# Sheet1.net
KiCad netlist of a schematic drawn in Altium Designer
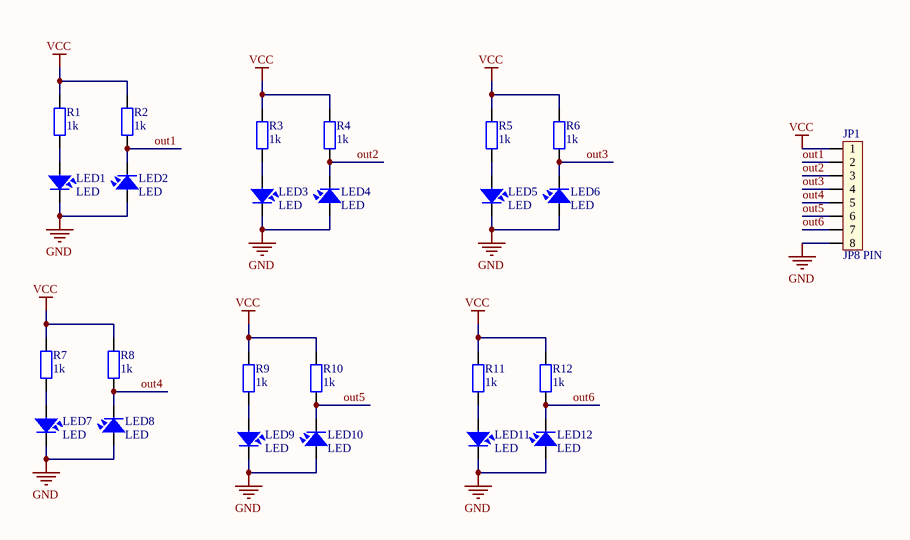
[diagram p0: Sheet1.SchDoc]

(export (version "E")
  (design (tool "Eeschema 10.0.6"))
  (components
    (comp (ref "JP1") (value "JP8 PIN") (footprint "JP8") (libsource (lib "syhaunguyen") (part "JP8")))
    (comp (ref "LED1")
      (value "LED")
      (footprint "LED-3")
      (description "LED Single colour Green and Red")
      (libsource (lib "syhaunguyen") (part "LED"))
    )
    (comp (ref "LED2")
      (value "LED")
      (footprint "LED-3")
      (description "LED Single colour Green and Red")
      (libsource (lib "syhaunguyen") (part "LED"))
    )
    (comp (ref "LED3")
      (value "LED")
      (footprint "LED-3")
      (description "LED Single colour Green and Red")
      (libsource (lib "syhaunguyen") (part "LED"))
    )
    (comp (ref "LED4")
      (value "LED")
      (footprint "LED-3")
      (description "LED Single colour Green and Red")
      (libsource (lib "syhaunguyen") (part "LED"))
    )
    (comp (ref "LED5")
      (value "LED")
      (footprint "LED-3")
      (description "LED Single colour Green and Red")
      (libsource (lib "syhaunguyen") (part "LED"))
    )
    (comp (ref "LED6")
      (value "LED")
      (footprint "LED-3")
      (description "LED Single colour Green and Red")
      (libsource (lib "syhaunguyen") (part "LED"))
    )
    (comp (ref "LED7")
      (value "LED")
      (footprint "LED-3")
      (description "LED Single colour Green and Red")
      (libsource (lib "syhaunguyen") (part "LED"))
    )
    (comp (ref "LED8")
      (value "LED")
      (footprint "LED-3")
      (description "LED Single colour Green and Red")
      (libsource (lib "syhaunguyen") (part "LED"))
    )
    (comp (ref "LED9")
      (value "LED")
      (footprint "LED-3")
      (description "LED Single colour Green and Red")
      (libsource (lib "syhaunguyen") (part "LED"))
    )
    (comp (ref "LED10")
      (value "LED")
      (footprint "LED-3")
      (description "LED Single colour Green and Red")
      (libsource (lib "syhaunguyen") (part "LED"))
    )
    (comp (ref "LED11")
      (value "LED")
      (footprint "LED-3")
      (description "LED Single colour Green and Red")
      (libsource (lib "syhaunguyen") (part "LED"))
    )
    (comp (ref "LED12")
      (value "LED")
      (footprint "LED-3")
      (description "LED Single colour Green and Red")
      (libsource (lib "syhaunguyen") (part "LED"))
    )
    (comp (ref "R1")
      (value "1k")
      (footprint "R1/4W")
      (description "Resistor 1/4W")
      (libsource (lib "syhaunguyen") (part "R1/4W"))
    )
    (comp (ref "R2")
      (value "1k")
      (footprint "R1/4W")
      (description "Resistor 1/4W")
      (libsource (lib "syhaunguyen") (part "R1/4W"))
    )
    (comp (ref "R3")
      (value "1k")
      (footprint "R1/4W")
      (description "Resistor 1/4W")
      (libsource (lib "syhaunguyen") (part "R1/4W"))
    )
    (comp (ref "R4")
      (value "1k")
      (footprint "R1/4W")
      (description "Resistor 1/4W")
      (libsource (lib "syhaunguyen") (part "R1/4W"))
    )
    (comp (ref "R5")
      (value "1k")
      (footprint "R1/4W")
      (description "Resistor 1/4W")
      (libsource (lib "syhaunguyen") (part "R1/4W"))
    )
    (comp (ref "R6")
      (value "1k")
      (footprint "R1/4W")
      (description "Resistor 1/4W")
      (libsource (lib "syhaunguyen") (part "R1/4W"))
    )
    (comp (ref "R7")
      (value "1k")
      (footprint "R1/4W")
      (description "Resistor 1/4W")
      (libsource (lib "syhaunguyen") (part "R1/4W"))
    )
    (comp (ref "R8")
      (value "1k")
      (footprint "R1/4W")
      (description "Resistor 1/4W")
      (libsource (lib "syhaunguyen") (part "R1/4W"))
    )
    (comp (ref "R9")
      (value "1k")
      (footprint "R1/4W")
      (description "Resistor 1/4W")
      (libsource (lib "syhaunguyen") (part "R1/4W"))
    )
    (comp (ref "R10")
      (value "1k")
      (footprint "R1/4W")
      (description "Resistor 1/4W")
      (libsource (lib "syhaunguyen") (part "R1/4W"))
    )
    (comp (ref "R11")
      (value "1k")
      (footprint "R1/4W")
      (description "Resistor 1/4W")
      (libsource (lib "syhaunguyen") (part "R1/4W"))
    )
    (comp (ref "R12")
      (value "1k")
      (footprint "R1/4W")
      (description "Resistor 1/4W")
      (libsource (lib "syhaunguyen") (part "R1/4W"))
    )
  )
  (nets
    (net (code "1") (name "/out1") (class "Default")
      (node (ref "JP1") (pin "2") (pinfunction "2_2") (pintype "passive"))
      (node (ref "LED2") (pin "2") (pinfunction "2_2") (pintype "passive"))
      (node (ref "R2") (pin "1") (pinfunction "1_1") (pintype "passive"))
    )
    (net (code "2") (name "/out2") (class "Default")
      (node (ref "JP1") (pin "3") (pinfunction "3_3") (pintype "passive"))
      (node (ref "LED4") (pin "2") (pinfunction "2_2") (pintype "passive"))
      (node (ref "R4") (pin "1") (pinfunction "1_1") (pintype "passive"))
    )
    (net (code "3") (name "/out3") (class "Default")
      (node (ref "JP1") (pin "4") (pinfunction "4_4") (pintype "passive"))
      (node (ref "LED6") (pin "2") (pinfunction "2_2") (pintype "passive"))
      (node (ref "R6") (pin "1") (pinfunction "1_1") (pintype "passive"))
    )
    (net (code "4") (name "/out4") (class "Default")
      (node (ref "JP1") (pin "5") (pinfunction "5_5") (pintype "passive"))
      (node (ref "LED8") (pin "2") (pinfunction "2_2") (pintype "passive"))
      (node (ref "R8") (pin "1") (pinfunction "1_1") (pintype "passive"))
    )
    (net (code "5") (name "/out5") (class "Default")
      (node (ref "JP1") (pin "6") (pinfunction "6_6") (pintype "passive"))
      (node (ref "LED10") (pin "2") (pinfunction "2_2") (pintype "passive"))
      (node (ref "R10") (pin "1") (pinfunction "1_1") (pintype "passive"))
    )
    (net (code "6") (name "/out6") (class "Default")
      (node (ref "JP1") (pin "7") (pinfunction "7_7") (pintype "passive"))
      (node (ref "LED12") (pin "2") (pinfunction "2_2") (pintype "passive"))
      (node (ref "R12") (pin "1") (pinfunction "1_1") (pintype "passive"))
    )
    (net (code "7") (name "GND") (class "Default")
      (node (ref "JP1") (pin "8") (pinfunction "8_8") (pintype "passive"))
      (node (ref "LED1") (pin "2") (pinfunction "2_2") (pintype "passive"))
      (node (ref "LED10") (pin "1") (pinfunction "1_1") (pintype "passive"))
      (node (ref "LED11") (pin "2") (pinfunction "2_2") (pintype "passive"))
      (node (ref "LED12") (pin "1") (pinfunction "1_1") (pintype "passive"))
      (node (ref "LED2") (pin "1") (pinfunction "1_1") (pintype "passive"))
      (node (ref "LED3") (pin "2") (pinfunction "2_2") (pintype "passive"))
      (node (ref "LED4") (pin "1") (pinfunction "1_1") (pintype "passive"))
      (node (ref "LED5") (pin "2") (pinfunction "2_2") (pintype "passive"))
      (node (ref "LED6") (pin "1") (pinfunction "1_1") (pintype "passive"))
      (node (ref "LED7") (pin "2") (pinfunction "2_2") (pintype "passive"))
      (node (ref "LED8") (pin "1") (pinfunction "1_1") (pintype "passive"))
      (node (ref "LED9") (pin "2") (pinfunction "2_2") (pintype "passive"))
    )
    (net (code "8") (name "Net-(LED1-Pad1)") (class "Default")
      (node (ref "LED1") (pin "1") (pinfunction "1_1") (pintype "passive"))
      (node (ref "R1") (pin "1") (pinfunction "1_1") (pintype "passive"))
    )
    (net (code "9") (name "Net-(LED3-Pad1)") (class "Default")
      (node (ref "LED3") (pin "1") (pinfunction "1_1") (pintype "passive"))
      (node (ref "R3") (pin "1") (pinfunction "1_1") (pintype "passive"))
    )
    (net (code "10") (name "Net-(LED5-Pad1)") (class "Default")
      (node (ref "LED5") (pin "1") (pinfunction "1_1") (pintype "passive"))
      (node (ref "R5") (pin "1") (pinfunction "1_1") (pintype "passive"))
    )
    (net (code "11") (name "Net-(LED7-Pad1)") (class "Default")
      (node (ref "LED7") (pin "1") (pinfunction "1_1") (pintype "passive"))
      (node (ref "R7") (pin "1") (pinfunction "1_1") (pintype "passive"))
    )
    (net (code "12") (name "Net-(LED9-Pad1)") (class "Default")
      (node (ref "LED9") (pin "1") (pinfunction "1_1") (pintype "passive"))
      (node (ref "R9") (pin "1") (pinfunction "1_1") (pintype "passive"))
    )
    (net (code "13") (name "Net-(LED11-Pad1)") (class "Default")
      (node (ref "LED11") (pin "1") (pinfunction "1_1") (pintype "passive"))
      (node (ref "R11") (pin "1") (pinfunction "1_1") (pintype "passive"))
    )
    (net (code "14") (name "VCC") (class "Default")
      (node (ref "JP1") (pin "1") (pinfunction "1_1") (pintype "passive"))
      (node (ref "R1") (pin "2") (pinfunction "2_2") (pintype "passive"))
      (node (ref "R10") (pin "2") (pinfunction "2_2") (pintype "passive"))
      (node (ref "R11") (pin "2") (pinfunction "2_2") (pintype "passive"))
      (node (ref "R12") (pin "2") (pinfunction "2_2") (pintype "passive"))
      (node (ref "R2") (pin "2") (pinfunction "2_2") (pintype "passive"))
      (node (ref "R3") (pin "2") (pinfunction "2_2") (pintype "passive"))
      (node (ref "R4") (pin "2") (pinfunction "2_2") (pintype "passive"))
      (node (ref "R5") (pin "2") (pinfunction "2_2") (pintype "passive"))
      (node (ref "R6") (pin "2") (pinfunction "2_2") (pintype "passive"))
      (node (ref "R7") (pin "2") (pinfunction "2_2") (pintype "passive"))
      (node (ref "R8") (pin "2") (pinfunction "2_2") (pintype "passive"))
      (node (ref "R9") (pin "2") (pinfunction "2_2") (pintype "passive"))
    )
  )
)
